# Encoder.net
KiCad netlist of a schematic drawn in Altium Designer
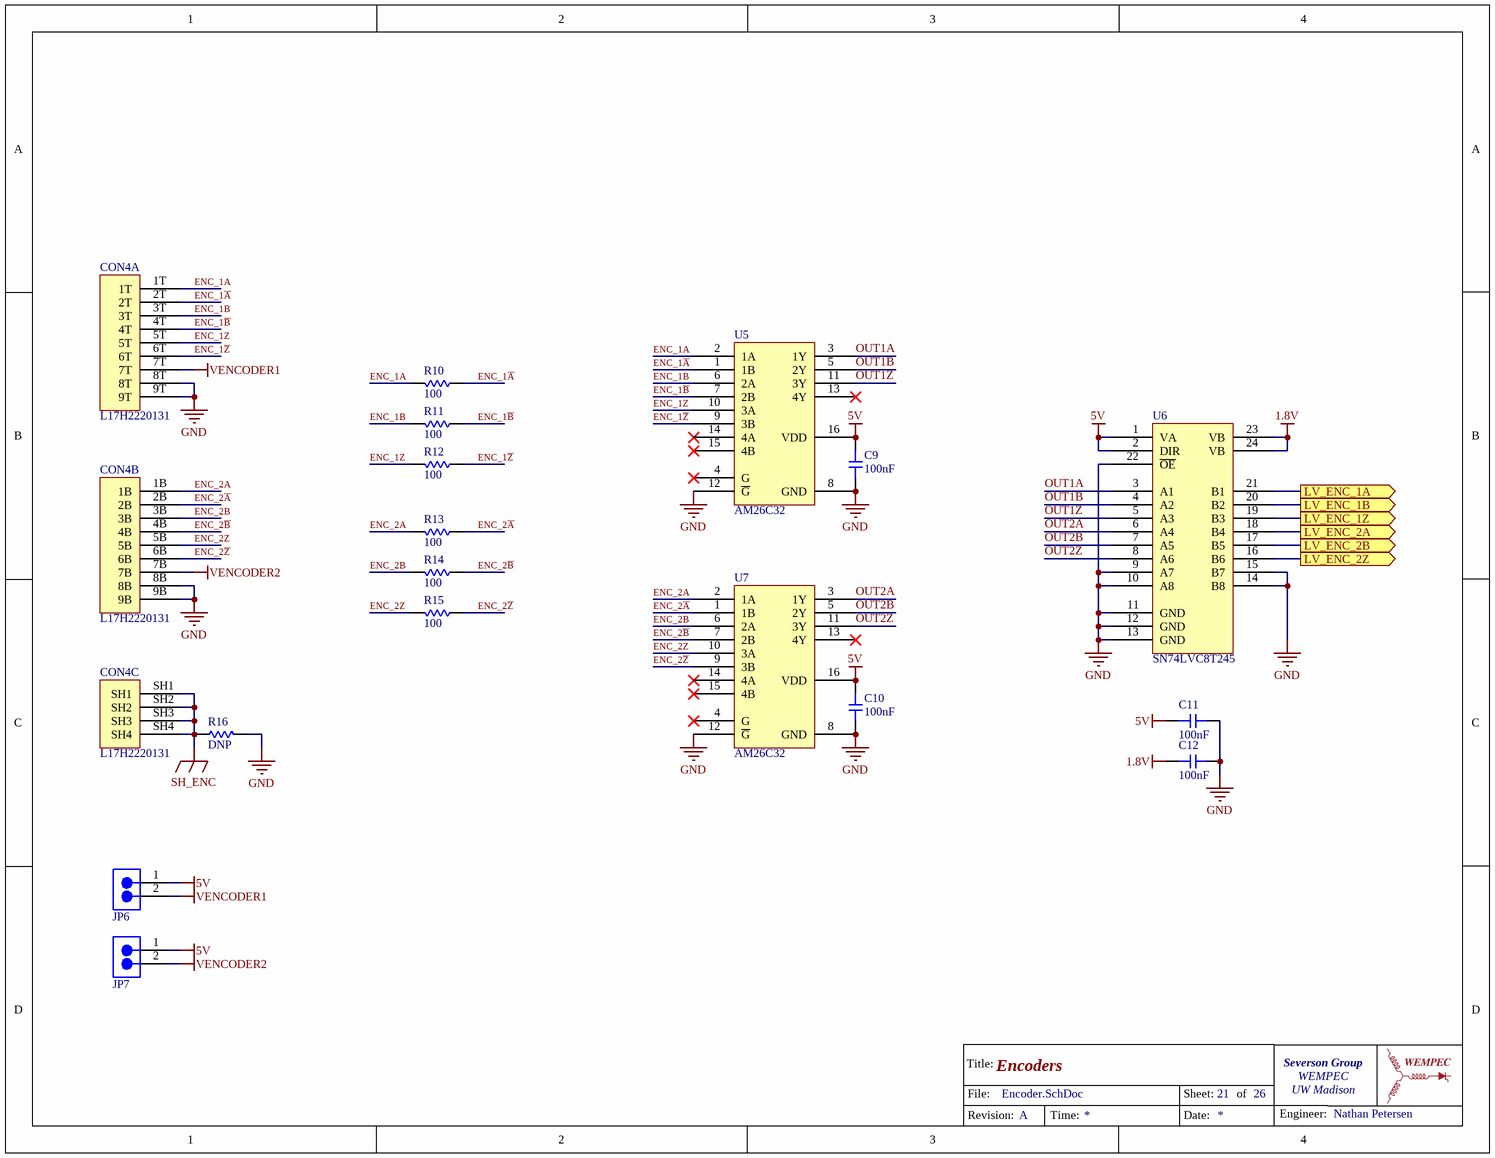
[diagram p0: Encoder.SchDoc]

(export (version "E")
  (design (tool "Eeschema 10.0.6"))
  (components
    (comp (ref "C9")
      (value "100nF")
      (footprint "AMDC:0603-CAP")
      (description "Capacitor")
      (libsource (lib "AMDC") (part "Capacitor"))
    )
    (comp (ref "C10")
      (value "100nF")
      (footprint "AMDC:0603-CAP")
      (description "Capacitor")
      (libsource (lib "AMDC") (part "Capacitor"))
    )
    (comp (ref "C11")
      (value "100nF")
      (footprint "AMDC:0603-CAP")
      (description "Capacitor")
      (libsource (lib "AMDC") (part "Capacitor"))
    )
    (comp (ref "C12")
      (value "100nF")
      (footprint "AMDC:0603-CAP")
      (description "Capacitor")
      (libsource (lib "AMDC") (part "Capacitor"))
    )
    (comp (ref "CON4")
      (value "L17H2220131")
      (footprint "AMDC:L17H2220131")
      (description "CONN D-SUB RCPT 9POS R/A SLDR")
      (libsource (lib "AMDC") (part "L17H2220131"))
    )
    (comp (ref "JP6")
      (value "Jumper2")
      (footprint "AMDC:PIN_HEADER_1x2")
      (libsource (lib "AMDC") (part "Jumper2"))
    )
    (comp (ref "JP7")
      (value "Jumper2")
      (footprint "AMDC:PIN_HEADER_1x2")
      (libsource (lib "AMDC") (part "Jumper2"))
    )
    (comp (ref "R10")
      (value "100")
      (footprint "AMDC:0603-RES")
      (description "Resistor")
      (libsource (lib "AMDC") (part "Resistor"))
    )
    (comp (ref "R11")
      (value "100")
      (footprint "AMDC:0603-RES")
      (description "Resistor")
      (libsource (lib "AMDC") (part "Resistor"))
    )
    (comp (ref "R12")
      (value "100")
      (footprint "AMDC:0603-RES")
      (description "Resistor")
      (libsource (lib "AMDC") (part "Resistor"))
    )
    (comp (ref "R13")
      (value "100")
      (footprint "AMDC:0603-RES")
      (description "Resistor")
      (libsource (lib "AMDC") (part "Resistor"))
    )
    (comp (ref "R14")
      (value "100")
      (footprint "AMDC:0603-RES")
      (description "Resistor")
      (libsource (lib "AMDC") (part "Resistor"))
    )
    (comp (ref "R15")
      (value "100")
      (footprint "AMDC:0603-RES")
      (description "Resistor")
      (libsource (lib "AMDC") (part "Resistor"))
    )
    (comp (ref "R16")
      (value "DNP")
      (footprint "AMDC:0603-RES")
      (description "Resistor")
      (libsource (lib "AMDC") (part "Resistor"))
    )
    (comp (ref "U5")
      (value "AM26C32")
      (footprint "AMDC:TSOP65P640X120-16N")
      (description "IC RCVR RS422 QUAD DIFF 16TSSOP")
      (libsource (lib "AMDC") (part "AM26C32"))
    )
    (comp (ref "U6")
      (value "SN74LVC8T245")
      (footprint "AMDC:TSOP65P640X120-24N")
      (description "IC BUS TRANSCVR 8BIT 24TSSOP")
      (libsource (lib "AMDC") (part "SN74LVC8T245PWR"))
    )
    (comp (ref "U7")
      (value "AM26C32")
      (footprint "AMDC:TSOP65P640X120-16N")
      (description "IC RCVR RS422 QUAD DIFF 16TSSOP")
      (libsource (lib "AMDC") (part "AM26C32"))
    )
  )
  (nets
    (net (code "1") (name "/ENC_1A") (class "Default")
      (node (ref "CON4") (pin "1T") (pinfunction "1T_1T") (pintype "passive"))
      (node (ref "R10") (pin "2") (pinfunction "2_2") (pintype "passive"))
      (node (ref "U5") (pin "2") (pinfunction "1A_2") (pintype "passive"))
    )
    (net (code "2") (name "/ENC_1B") (class "Default")
      (node (ref "CON4") (pin "3T") (pinfunction "3T_3T") (pintype "passive"))
      (node (ref "R11") (pin "2") (pinfunction "2_2") (pintype "passive"))
      (node (ref "U5") (pin "6") (pinfunction "2A_6") (pintype "passive"))
    )
    (net (code "3") (name "/ENC_1Z") (class "Default")
      (node (ref "CON4") (pin "5T") (pinfunction "5T_5T") (pintype "passive"))
      (node (ref "R12") (pin "2") (pinfunction "2_2") (pintype "passive"))
      (node (ref "U5") (pin "10") (pinfunction "3A_10") (pintype "passive"))
    )
    (net (code "4") (name "/ENC_1~{A}") (class "Default")
      (node (ref "CON4") (pin "2T") (pinfunction "2T_2T") (pintype "passive"))
      (node (ref "R10") (pin "1") (pinfunction "1_1") (pintype "passive"))
      (node (ref "U5") (pin "1") (pinfunction "1B_1") (pintype "passive"))
    )
    (net (code "5") (name "/ENC_1~{B}") (class "Default")
      (node (ref "CON4") (pin "4T") (pinfunction "4T_4T") (pintype "passive"))
      (node (ref "R11") (pin "1") (pinfunction "1_1") (pintype "passive"))
      (node (ref "U5") (pin "7") (pinfunction "2B_7") (pintype "passive"))
    )
    (net (code "6") (name "/ENC_1~{Z}") (class "Default")
      (node (ref "CON4") (pin "6T") (pinfunction "6T_6T") (pintype "passive"))
      (node (ref "R12") (pin "1") (pinfunction "1_1") (pintype "passive"))
      (node (ref "U5") (pin "9") (pinfunction "3B_9") (pintype "passive"))
    )
    (net (code "7") (name "/ENC_2A") (class "Default")
      (node (ref "CON4") (pin "1B") (pinfunction "1B_1B") (pintype "passive"))
      (node (ref "R13") (pin "2") (pinfunction "2_2") (pintype "passive"))
      (node (ref "U7") (pin "2") (pinfunction "1A_2") (pintype "passive"))
    )
    (net (code "8") (name "/ENC_2B") (class "Default")
      (node (ref "CON4") (pin "3B") (pinfunction "3B_3B") (pintype "passive"))
      (node (ref "R14") (pin "2") (pinfunction "2_2") (pintype "passive"))
      (node (ref "U7") (pin "6") (pinfunction "2A_6") (pintype "passive"))
    )
    (net (code "9") (name "/ENC_2Z") (class "Default")
      (node (ref "CON4") (pin "5B") (pinfunction "5B_5B") (pintype "passive"))
      (node (ref "R15") (pin "2") (pinfunction "2_2") (pintype "passive"))
      (node (ref "U7") (pin "10") (pinfunction "3A_10") (pintype "passive"))
    )
    (net (code "10") (name "/ENC_2~{A}") (class "Default")
      (node (ref "CON4") (pin "2B") (pinfunction "2B_2B") (pintype "passive"))
      (node (ref "R13") (pin "1") (pinfunction "1_1") (pintype "passive"))
      (node (ref "U7") (pin "1") (pinfunction "1B_1") (pintype "passive"))
    )
    (net (code "11") (name "/ENC_2~{B}") (class "Default")
      (node (ref "CON4") (pin "4B") (pinfunction "4B_4B") (pintype "passive"))
      (node (ref "R14") (pin "1") (pinfunction "1_1") (pintype "passive"))
      (node (ref "U7") (pin "7") (pinfunction "2B_7") (pintype "passive"))
    )
    (net (code "12") (name "/ENC_2~{Z}") (class "Default")
      (node (ref "CON4") (pin "6B") (pinfunction "6B_6B") (pintype "passive"))
      (node (ref "R15") (pin "1") (pinfunction "1_1") (pintype "passive"))
      (node (ref "U7") (pin "9") (pinfunction "3B_9") (pintype "passive"))
    )
    (net (code "13") (name "/LV_ENC_1A") (class "Default")
      (node (ref "U6") (pin "21") (pinfunction "B1_21") (pintype "passive"))
    )
    (net (code "14") (name "/LV_ENC_1B") (class "Default")
      (node (ref "U6") (pin "20") (pinfunction "B2_20") (pintype "passive"))
    )
    (net (code "15") (name "/LV_ENC_1Z") (class "Default")
      (node (ref "U6") (pin "19") (pinfunction "B3_19") (pintype "passive"))
    )
    (net (code "16") (name "/LV_ENC_2A") (class "Default")
      (node (ref "U6") (pin "18") (pinfunction "B4_18") (pintype "passive"))
    )
    (net (code "17") (name "/LV_ENC_2B") (class "Default")
      (node (ref "U6") (pin "17") (pinfunction "B5_17") (pintype "passive"))
    )
    (net (code "18") (name "/LV_ENC_2Z") (class "Default")
      (node (ref "U6") (pin "16") (pinfunction "B6_16") (pintype "passive"))
    )
    (net (code "19") (name "/OUT1A") (class "Default")
      (node (ref "U5") (pin "3") (pinfunction "1Y_3") (pintype "passive"))
      (node (ref "U6") (pin "3") (pinfunction "A1_3") (pintype "passive"))
    )
    (net (code "20") (name "/OUT1B") (class "Default")
      (node (ref "U5") (pin "5") (pinfunction "2Y_5") (pintype "passive"))
      (node (ref "U6") (pin "4") (pinfunction "A2_4") (pintype "passive"))
    )
    (net (code "21") (name "/OUT1Z") (class "Default")
      (node (ref "U5") (pin "11") (pinfunction "3Y_11") (pintype "passive"))
      (node (ref "U6") (pin "5") (pinfunction "A3_5") (pintype "passive"))
    )
    (net (code "22") (name "/OUT2A") (class "Default")
      (node (ref "U6") (pin "6") (pinfunction "A4_6") (pintype "passive"))
      (node (ref "U7") (pin "3") (pinfunction "1Y_3") (pintype "passive"))
    )
    (net (code "23") (name "/OUT2B") (class "Default")
      (node (ref "U6") (pin "7") (pinfunction "A5_7") (pintype "passive"))
      (node (ref "U7") (pin "5") (pinfunction "2Y_5") (pintype "passive"))
    )
    (net (code "24") (name "/OUT2Z") (class "Default")
      (node (ref "U6") (pin "8") (pinfunction "A6_8") (pintype "passive"))
      (node (ref "U7") (pin "11") (pinfunction "3Y_11") (pintype "passive"))
    )
    (net (code "25") (name "1.8V") (class "Default")
      (node (ref "C12") (pin "1") (pinfunction "1_1") (pintype "passive"))
      (node (ref "U6") (pin "23") (pinfunction "VB_23") (pintype "passive"))
      (node (ref "U6") (pin "24") (pinfunction "VB_24") (pintype "passive"))
    )
    (net (code "26") (name "5V") (class "Default")
      (node (ref "C10") (pin "2") (pinfunction "2_2") (pintype "passive"))
      (node (ref "C11") (pin "1") (pinfunction "1_1") (pintype "passive"))
      (node (ref "C9") (pin "2") (pinfunction "2_2") (pintype "passive"))
      (node (ref "JP6") (pin "1") (pinfunction "76_1") (pintype "passive"))
      (node (ref "JP7") (pin "1") (pinfunction "76_1") (pintype "passive"))
      (node (ref "U5") (pin "16") (pinfunction "VDD_16") (pintype "passive"))
      (node (ref "U6") (pin "1") (pinfunction "VA_1") (pintype "passive"))
      (node (ref "U6") (pin "2") (pinfunction "DIR_2") (pintype "passive"))
      (node (ref "U7") (pin "16") (pinfunction "VDD_16") (pintype "passive"))
    )
    (net (code "27") (name "GND") (class "Default")
      (node (ref "C10") (pin "1") (pinfunction "1_1") (pintype "passive"))
      (node (ref "C11") (pin "2") (pinfunction "2_2") (pintype "passive"))
      (node (ref "C12") (pin "2") (pinfunction "2_2") (pintype "passive"))
      (node (ref "C9") (pin "1") (pinfunction "1_1") (pintype "passive"))
      (node (ref "CON4") (pin "8B") (pinfunction "8B_8B") (pintype "passive"))
      (node (ref "CON4") (pin "8T") (pinfunction "8T_8T") (pintype "passive"))
      (node (ref "CON4") (pin "9B") (pinfunction "9B_9B") (pintype "passive"))
      (node (ref "CON4") (pin "9T") (pinfunction "9T_9T") (pintype "passive"))
      (node (ref "R16") (pin "2") (pinfunction "2_2") (pintype "passive"))
      (node (ref "U5") (pin "12") (pinfunction "~{G}_12") (pintype "passive"))
      (node (ref "U5") (pin "8") (pinfunction "GND_8") (pintype "passive"))
      (node (ref "U6") (pin "10") (pinfunction "A8_10") (pintype "passive"))
      (node (ref "U6") (pin "11") (pinfunction "GND_11") (pintype "passive"))
      (node (ref "U6") (pin "12") (pinfunction "GND_12") (pintype "passive"))
      (node (ref "U6") (pin "13") (pinfunction "GND_13") (pintype "passive"))
      (node (ref "U6") (pin "14") (pinfunction "B8_14") (pintype "passive"))
      (node (ref "U6") (pin "15") (pinfunction "B7_15") (pintype "passive"))
      (node (ref "U6") (pin "22") (pinfunction "~{OE}_22") (pintype "passive"))
      (node (ref "U6") (pin "9") (pinfunction "A7_9") (pintype "passive"))
      (node (ref "U7") (pin "12") (pinfunction "~{G}_12") (pintype "passive"))
      (node (ref "U7") (pin "8") (pinfunction "GND_8") (pintype "passive"))
    )
    (net (code "28") (name "SH_ENC") (class "Default")
      (node (ref "CON4") (pin "SH1") (pinfunction "SH1_SH1") (pintype "passive"))
      (node (ref "CON4") (pin "SH2") (pinfunction "SH2_SH2") (pintype "passive"))
      (node (ref "CON4") (pin "SH3") (pinfunction "SH3_SH3") (pintype "passive"))
      (node (ref "CON4") (pin "SH4") (pinfunction "SH4_SH4") (pintype "passive"))
      (node (ref "R16") (pin "1") (pinfunction "1_1") (pintype "passive"))
    )
    (net (code "29") (name "VENCODER1") (class "Default")
      (node (ref "CON4") (pin "7T") (pinfunction "7T_7T") (pintype "passive"))
      (node (ref "JP6") (pin "2") (pinfunction "75_2") (pintype "passive"))
    )
    (net (code "30") (name "VENCODER2") (class "Default")
      (node (ref "CON4") (pin "7B") (pinfunction "7B_7B") (pintype "passive"))
      (node (ref "JP7") (pin "2") (pinfunction "75_2") (pintype "passive"))
    )
    (net (code "31") (name "unconnected-(U5-4A-Pad14)") (class "Default")
      (node (ref "U5") (pin "14") (pinfunction "4A_14") (pintype "passive+no_connect"))
    )
    (net (code "32") (name "unconnected-(U5-4B-Pad15)") (class "Default")
      (node (ref "U5") (pin "15") (pinfunction "4B_15") (pintype "passive+no_connect"))
    )
    (net (code "33") (name "unconnected-(U5-4Y-Pad13)") (class "Default")
      (node (ref "U5") (pin "13") (pinfunction "4Y_13") (pintype "passive+no_connect"))
    )
    (net (code "34") (name "unconnected-(U5-G-Pad4)") (class "Default")
      (node (ref "U5") (pin "4") (pinfunction "G_4") (pintype "passive+no_connect"))
    )
    (net (code "35") (name "unconnected-(U7-4A-Pad14)") (class "Default")
      (node (ref "U7") (pin "14") (pinfunction "4A_14") (pintype "passive+no_connect"))
    )
    (net (code "36") (name "unconnected-(U7-4B-Pad15)") (class "Default")
      (node (ref "U7") (pin "15") (pinfunction "4B_15") (pintype "passive+no_connect"))
    )
    (net (code "37") (name "unconnected-(U7-4Y-Pad13)") (class "Default")
      (node (ref "U7") (pin "13") (pinfunction "4Y_13") (pintype "passive+no_connect"))
    )
    (net (code "38") (name "unconnected-(U7-G-Pad4)") (class "Default")
      (node (ref "U7") (pin "4") (pinfunction "G_4") (pintype "passive+no_connect"))
    )
  )
)
